# 18650_1S3P.net
KiCad netlist of a schematic drawn in EAGLE
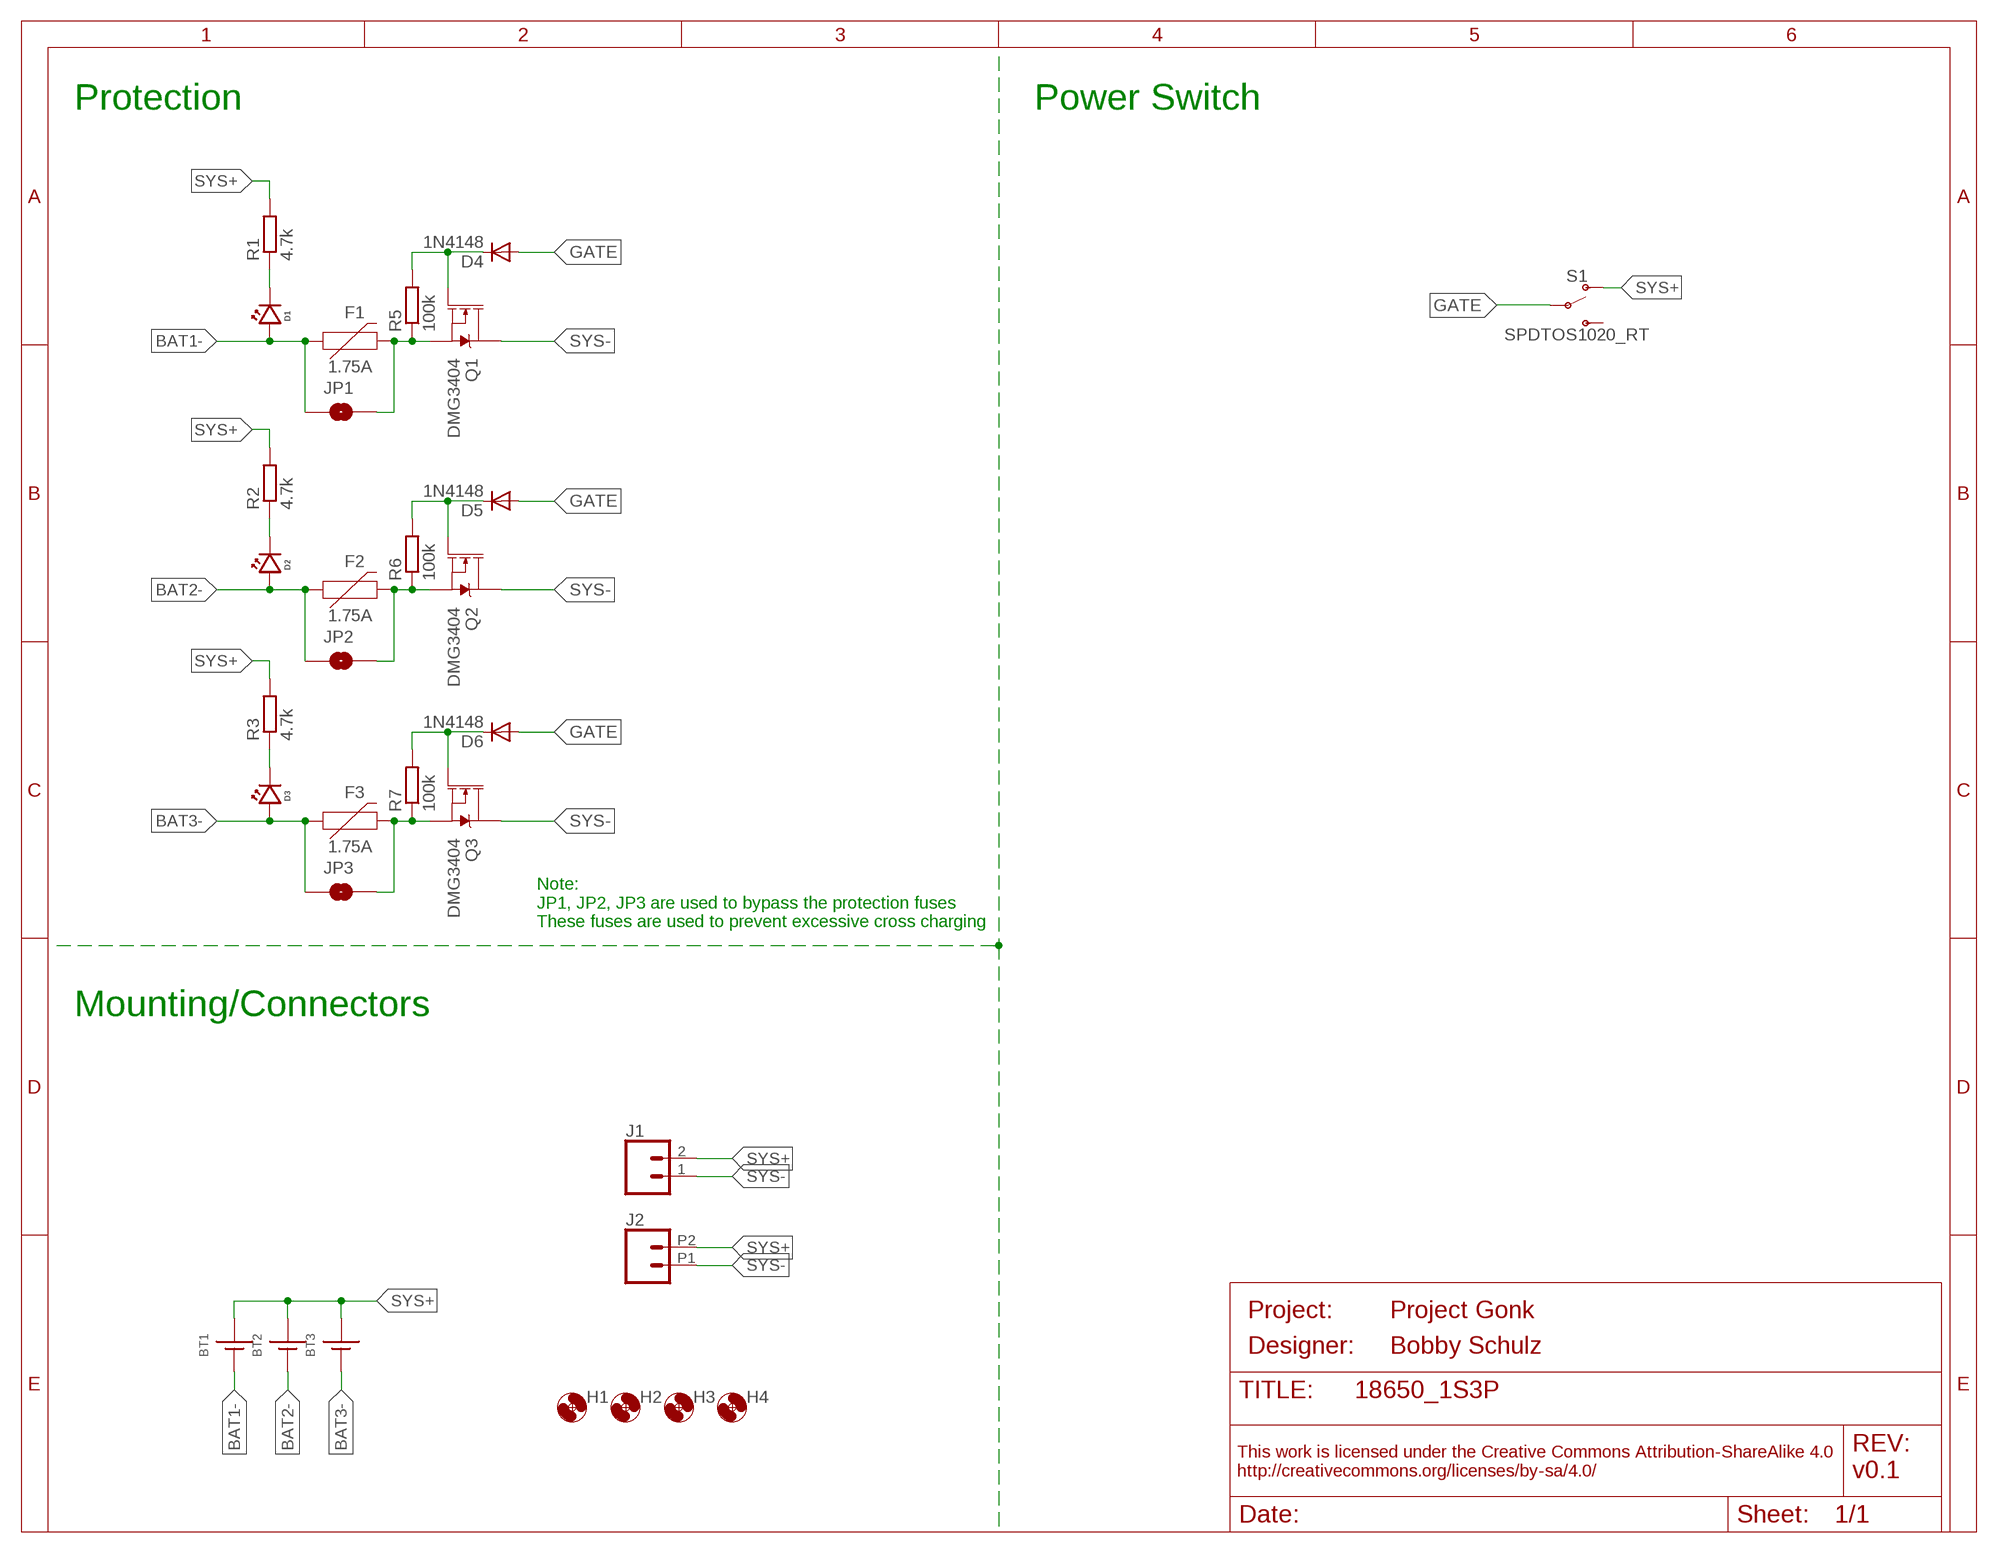
[diagram p0: schematic, sheet 1]

(export (version "E")
  (design (tool "Eeschema 10.0.6"))
  (components
    (comp (ref "BT1")
      (value "18650NO_PROTEC")
      (footprint "eagle-import:BATT_18650_CLIP")
      (fields (field (name "MF") "Keystone") (field (name "MPN") "54"))
      (libsource (lib "eagle-import") (part "18650NO_PROTEC"))
    )
    (comp (ref "BT2")
      (value "18650NO_PROTEC")
      (footprint "eagle-import:BATT_18650_CLIP")
      (fields (field (name "MF") "Keystone") (field (name "MPN") "54"))
      (libsource (lib "eagle-import") (part "18650NO_PROTEC"))
    )
    (comp (ref "BT3")
      (value "18650NO_PROTEC")
      (footprint "eagle-import:BATT_18650_CLIP")
      (fields (field (name "MF") "Keystone") (field (name "MPN") "54"))
      (libsource (lib "eagle-import") (part "18650NO_PROTEC"))
    )
    (comp (ref "D1")
      (value "LED0805")
      (footprint "eagle-import:LED_0805")
      (fields (field (name "MF") "OSRAM") (field (name "MPN") "LS R976-NR-1"))
      (libsource (lib "eagle-import") (part "LED0805"))
    )
    (comp (ref "D2")
      (value "LED0805")
      (footprint "eagle-import:LED_0805")
      (fields (field (name "MF") "OSRAM") (field (name "MPN") "LS R976-NR-1"))
      (libsource (lib "eagle-import") (part "LED0805"))
    )
    (comp (ref "D3")
      (value "LED0805")
      (footprint "eagle-import:LED_0805")
      (fields (field (name "MF") "OSRAM") (field (name "MPN") "LS R976-NR-1"))
      (libsource (lib "eagle-import") (part "LED0805"))
    )
    (comp (ref "D4")
      (value "1N4148")
      (footprint "eagle-import:SOD323-R")
      (fields
        (field (name "DIGIKEY") "1N4148WS-FDICT-ND")
        (field (name "MF") "Diodes Inc")
        (field (name "MPN") "1N4148WS-7-F")
      )
      (libsource (lib "eagle-import") (part "DIODESOD-323"))
    )
    (comp (ref "D5")
      (value "1N4148")
      (footprint "eagle-import:SOD323-R")
      (fields
        (field (name "DIGIKEY") "1N4148WS-FDICT-ND")
        (field (name "MF") "Diodes Inc")
        (field (name "MPN") "1N4148WS-7-F")
      )
      (libsource (lib "eagle-import") (part "DIODESOD-323"))
    )
    (comp (ref "D6")
      (value "1N4148")
      (footprint "eagle-import:SOD323-R")
      (fields
        (field (name "DIGIKEY") "1N4148WS-FDICT-ND")
        (field (name "MF") "Diodes Inc")
        (field (name "MPN") "1N4148WS-7-F")
      )
      (libsource (lib "eagle-import") (part "DIODESOD-323"))
    )
    (comp (ref "F1")
      (value "1.75A")
      (footprint "eagle-import:1210_BOURNS")
      (fields (field (name "MF") "Bourns") (field (name "MPN") "MF-USMF175X-2"))
      (libsource (lib "eagle-import") (part "PPTC12101.75A"))
    )
    (comp (ref "F2")
      (value "1.75A")
      (footprint "eagle-import:1210_BOURNS")
      (fields (field (name "MF") "Bourns") (field (name "MPN") "MF-USMF175X-2"))
      (libsource (lib "eagle-import") (part "PPTC12101.75A"))
    )
    (comp (ref "F3")
      (value "1.75A")
      (footprint "eagle-import:1210_BOURNS")
      (fields (field (name "MF") "Bourns") (field (name "MPN") "MF-USMF175X-2"))
      (libsource (lib "eagle-import") (part "PPTC12101.75A"))
    )
    (comp (ref "H1")
      (value "MOUNTING_HOLE4_NP")
      (footprint "eagle-import:4_40")
      (fields (field (name "MPN") "DNP"))
      (libsource (lib "eagle-import") (part "MOUNTING_HOLE4_NP"))
    )
    (comp (ref "H2")
      (value "MOUNTING_HOLE4_NP")
      (footprint "eagle-import:4_40")
      (fields (field (name "MPN") "DNP"))
      (libsource (lib "eagle-import") (part "MOUNTING_HOLE4_NP"))
    )
    (comp (ref "H3")
      (value "MOUNTING_HOLE4_NP")
      (footprint "eagle-import:4_40")
      (fields (field (name "MPN") "DNP"))
      (libsource (lib "eagle-import") (part "MOUNTING_HOLE4_NP"))
    )
    (comp (ref "H4")
      (value "MOUNTING_HOLE4_NP")
      (footprint "eagle-import:4_40")
      (fields (field (name "MPN") "DNP"))
      (libsource (lib "eagle-import") (part "MOUNTING_HOLE4_NP"))
    )
    (comp (ref "J1")
      (value "CONN_023.5MM_ROUND_RESTRICT")
      (footprint "eagle-import:SCREWTERMINAL-3.5MM-2_ROUND_RESTRICT")
      (fields (field (name "MF") "On Shore") (field (name "MPN") "OSTTE020161"))
      (libsource (lib "eagle-import") (part "CONN_023.5MM_ROUND_RESTRICT"))
    )
    (comp (ref "J2")
      (value "CONN_022.54_SCREW_ROUND")
      (footprint "eagle-import:1X02_2.54_SCREWTERM_ROUND")
      (fields (field (name "MF") "OnShore") (field (name "MPN") "OSTVN02A150"))
      (libsource (lib "eagle-import") (part "CONN_022.54_SCREW_ROUND"))
    )
    (comp (ref "JP1")
      (value "JUMPER-SMT_2_NO_SILK")
      (footprint "eagle-import:SMT-JUMPER_2_NO_SILK")
      (libsource (lib "eagle-import") (part "JUMPER-SMT_2_NO_SILK"))
    )
    (comp (ref "JP2")
      (value "JUMPER-SMT_2_NO_SILK")
      (footprint "eagle-import:SMT-JUMPER_2_NO_SILK")
      (libsource (lib "eagle-import") (part "JUMPER-SMT_2_NO_SILK"))
    )
    (comp (ref "JP3")
      (value "JUMPER-SMT_2_NO_SILK")
      (footprint "eagle-import:SMT-JUMPER_2_NO_SILK")
      (libsource (lib "eagle-import") (part "JUMPER-SMT_2_NO_SILK"))
    )
    (comp (ref "Q1")
      (value "DMG3404")
      (footprint "eagle-import:SOT23-3")
      (fields (field (name "MF") "Diodes Incorporated") (field (name "MPN") "DMG3404L-7"))
      (libsource (lib "eagle-import") (part "MOSFET-NCH-DMG3404L"))
    )
    (comp (ref "Q2")
      (value "DMG3404")
      (footprint "eagle-import:SOT23-3")
      (fields (field (name "MF") "Diodes Incorporated") (field (name "MPN") "DMG3404L-7"))
      (libsource (lib "eagle-import") (part "MOSFET-NCH-DMG3404L"))
    )
    (comp (ref "Q3")
      (value "DMG3404")
      (footprint "eagle-import:SOT23-3")
      (fields (field (name "MF") "Diodes Incorporated") (field (name "MPN") "DMG3404L-7"))
      (libsource (lib "eagle-import") (part "MOSFET-NCH-DMG3404L"))
    )
    (comp (ref "R1")
      (value "4.7k")
      (footprint "eagle-import:R0603")
      (fields (field (name "MF") "Yageo") (field (name "MPN") "RC0603FR-074K7L"))
      (libsource (lib "eagle-import") (part "R-EU_R06034.7K"))
    )
    (comp (ref "R2")
      (value "4.7k")
      (footprint "eagle-import:R0603")
      (fields (field (name "MF") "Yageo") (field (name "MPN") "RC0603FR-074K7L"))
      (libsource (lib "eagle-import") (part "R-EU_R06034.7K"))
    )
    (comp (ref "R3")
      (value "4.7k")
      (footprint "eagle-import:R0603")
      (fields (field (name "MF") "Yageo") (field (name "MPN") "RC0603FR-074K7L"))
      (libsource (lib "eagle-import") (part "R-EU_R06034.7K"))
    )
    (comp (ref "R5")
      (value "100k")
      (footprint "eagle-import:R0603")
      (fields (field (name "MF") "Yageo") (field (name "MPN") "RC0603FR-07100KL"))
      (libsource (lib "eagle-import") (part "R-EU_R0603100K"))
    )
    (comp (ref "R6")
      (value "100k")
      (footprint "eagle-import:R0603")
      (fields (field (name "MF") "Yageo") (field (name "MPN") "RC0603FR-07100KL"))
      (libsource (lib "eagle-import") (part "R-EU_R0603100K"))
    )
    (comp (ref "R7")
      (value "100k")
      (footprint "eagle-import:R0603")
      (fields (field (name "MF") "Yageo") (field (name "MPN") "RC0603FR-07100KL"))
      (libsource (lib "eagle-import") (part "R-EU_R0603100K"))
    )
    (comp (ref "S1")
      (value "SPDTOS1020_RT")
      (footprint "eagle-import:OS102011MA1QN1")
      (fields (field (name "MF") "C&K") (field (name "MPN") "OS102011MA1QN1"))
      (libsource (lib "eagle-import") (part "SPDTOS1020_RT"))
    )
  )
  (nets
    (net (code "1") (name "BAT1-") (class "Default")
      (node (ref "BT1") (pin "BATT-@1") (pinfunction "-_BATT-@1") (pintype "bidirectional"))
      (node (ref "BT1") (pin "BATT-@2") (pinfunction "-_BATT-@2") (pintype "bidirectional"))
      (node (ref "BT1") (pin "BATT-@3") (pinfunction "-_BATT-@3") (pintype "bidirectional"))
      (node (ref "D1") (pin "ANODE") (pinfunction "ANODE_ANODE") (pintype "power_in"))
      (node (ref "F1") (pin "1") (pinfunction "1_1") (pintype "bidirectional"))
      (node (ref "JP1") (pin "1") (pinfunction "1_1") (pintype "passive"))
    )
    (net (code "2") (name "BAT2-") (class "Default")
      (node (ref "BT2") (pin "BATT-@1") (pinfunction "-_BATT-@1") (pintype "bidirectional"))
      (node (ref "BT2") (pin "BATT-@2") (pinfunction "-_BATT-@2") (pintype "bidirectional"))
      (node (ref "BT2") (pin "BATT-@3") (pinfunction "-_BATT-@3") (pintype "bidirectional"))
      (node (ref "D2") (pin "ANODE") (pinfunction "ANODE_ANODE") (pintype "power_in"))
      (node (ref "F2") (pin "1") (pinfunction "1_1") (pintype "bidirectional"))
      (node (ref "JP2") (pin "1") (pinfunction "1_1") (pintype "passive"))
    )
    (net (code "3") (name "BAT3-") (class "Default")
      (node (ref "BT3") (pin "BATT-@1") (pinfunction "-_BATT-@1") (pintype "bidirectional"))
      (node (ref "BT3") (pin "BATT-@2") (pinfunction "-_BATT-@2") (pintype "bidirectional"))
      (node (ref "BT3") (pin "BATT-@3") (pinfunction "-_BATT-@3") (pintype "bidirectional"))
      (node (ref "D3") (pin "ANODE") (pinfunction "ANODE_ANODE") (pintype "power_in"))
      (node (ref "F3") (pin "1") (pinfunction "1_1") (pintype "bidirectional"))
      (node (ref "JP3") (pin "1") (pinfunction "1_1") (pintype "passive"))
    )
    (net (code "4") (name "GATE") (class "Default")
      (node (ref "D4") (pin "A") (pinfunction "A_A") (pintype "passive"))
      (node (ref "D5") (pin "A") (pinfunction "A_A") (pintype "passive"))
      (node (ref "D6") (pin "A") (pinfunction "A_A") (pintype "passive"))
      (node (ref "S1") (pin "2") (pinfunction "P_2") (pintype "passive"))
    )
    (net (code "5") (name "Net-(D1-PadCATHODE)") (class "Default")
      (node (ref "D1") (pin "CATHODE") (pinfunction "CATHODE_CATHODE") (pintype "power_in"))
      (node (ref "R1") (pin "1") (pinfunction "1_1") (pintype "passive"))
    )
    (net (code "6") (name "Net-(D2-PadCATHODE)") (class "Default")
      (node (ref "D2") (pin "CATHODE") (pinfunction "CATHODE_CATHODE") (pintype "power_in"))
      (node (ref "R2") (pin "1") (pinfunction "1_1") (pintype "passive"))
    )
    (net (code "7") (name "Net-(D3-PadCATHODE)") (class "Default")
      (node (ref "D3") (pin "CATHODE") (pinfunction "CATHODE_CATHODE") (pintype "power_in"))
      (node (ref "R3") (pin "1") (pinfunction "1_1") (pintype "passive"))
    )
    (net (code "8") (name "Net-(Q1-G)") (class "Default")
      (node (ref "D4") (pin "C") (pinfunction "C_C") (pintype "passive"))
      (node (ref "Q1") (pin "1") (pinfunction "G_1") (pintype "bidirectional"))
      (node (ref "R5") (pin "2") (pinfunction "2_2") (pintype "passive"))
    )
    (net (code "9") (name "Net-(Q1-S)") (class "Default")
      (node (ref "F1") (pin "2") (pinfunction "2_2") (pintype "bidirectional"))
      (node (ref "JP1") (pin "2") (pinfunction "2_2") (pintype "passive"))
      (node (ref "Q1") (pin "2") (pinfunction "S_2") (pintype "bidirectional"))
      (node (ref "R5") (pin "1") (pinfunction "1_1") (pintype "passive"))
    )
    (net (code "10") (name "Net-(Q2-G)") (class "Default")
      (node (ref "D5") (pin "C") (pinfunction "C_C") (pintype "passive"))
      (node (ref "Q2") (pin "1") (pinfunction "G_1") (pintype "bidirectional"))
      (node (ref "R6") (pin "2") (pinfunction "2_2") (pintype "passive"))
    )
    (net (code "11") (name "Net-(Q2-S)") (class "Default")
      (node (ref "F2") (pin "2") (pinfunction "2_2") (pintype "bidirectional"))
      (node (ref "JP2") (pin "2") (pinfunction "2_2") (pintype "passive"))
      (node (ref "Q2") (pin "2") (pinfunction "S_2") (pintype "bidirectional"))
      (node (ref "R6") (pin "1") (pinfunction "1_1") (pintype "passive"))
    )
    (net (code "12") (name "Net-(Q3-G)") (class "Default")
      (node (ref "D6") (pin "C") (pinfunction "C_C") (pintype "passive"))
      (node (ref "Q3") (pin "1") (pinfunction "G_1") (pintype "bidirectional"))
      (node (ref "R7") (pin "2") (pinfunction "2_2") (pintype "passive"))
    )
    (net (code "13") (name "Net-(Q3-S)") (class "Default")
      (node (ref "F3") (pin "2") (pinfunction "2_2") (pintype "bidirectional"))
      (node (ref "JP3") (pin "2") (pinfunction "2_2") (pintype "passive"))
      (node (ref "Q3") (pin "2") (pinfunction "S_2") (pintype "bidirectional"))
      (node (ref "R7") (pin "1") (pinfunction "1_1") (pintype "passive"))
    )
    (net (code "14") (name "SYS+") (class "Default")
      (node (ref "BT1") (pin "BATT+@1") (pinfunction "+_BATT+@1") (pintype "bidirectional"))
      (node (ref "BT1") (pin "BATT+@2") (pinfunction "+_BATT+@2") (pintype "bidirectional"))
      (node (ref "BT1") (pin "BATT+@3") (pinfunction "+_BATT+@3") (pintype "bidirectional"))
      (node (ref "BT2") (pin "BATT+@1") (pinfunction "+_BATT+@1") (pintype "bidirectional"))
      (node (ref "BT2") (pin "BATT+@2") (pinfunction "+_BATT+@2") (pintype "bidirectional"))
      (node (ref "BT2") (pin "BATT+@3") (pinfunction "+_BATT+@3") (pintype "bidirectional"))
      (node (ref "BT3") (pin "BATT+@1") (pinfunction "+_BATT+@1") (pintype "bidirectional"))
      (node (ref "BT3") (pin "BATT+@2") (pinfunction "+_BATT+@2") (pintype "bidirectional"))
      (node (ref "BT3") (pin "BATT+@3") (pinfunction "+_BATT+@3") (pintype "bidirectional"))
      (node (ref "J1") (pin "2") (pinfunction "2_2") (pintype "passive"))
      (node (ref "J2") (pin "P2") (pinfunction "2_P2") (pintype "passive"))
      (node (ref "R1") (pin "2") (pinfunction "2_2") (pintype "passive"))
      (node (ref "R2") (pin "2") (pinfunction "2_2") (pintype "passive"))
      (node (ref "R3") (pin "2") (pinfunction "2_2") (pintype "passive"))
      (node (ref "S1") (pin "1") (pinfunction "O_1") (pintype "passive"))
    )
    (net (code "15") (name "SYS-") (class "Default")
      (node (ref "J1") (pin "1") (pinfunction "1_1") (pintype "passive"))
      (node (ref "J2") (pin "P1") (pinfunction "1_P1") (pintype "passive"))
      (node (ref "Q1") (pin "3") (pinfunction "D_3") (pintype "bidirectional"))
      (node (ref "Q2") (pin "3") (pinfunction "D_3") (pintype "bidirectional"))
      (node (ref "Q3") (pin "3") (pinfunction "D_3") (pintype "bidirectional"))
    )
    (net (code "16") (name "unconnected-(S1-S-Pad3)") (class "Default")
      (node (ref "S1") (pin "3") (pinfunction "S_3") (pintype "passive"))
    )
  )
)
